# BadgeSMD3.net
KiCad netlist of a schematic drawn in EAGLE
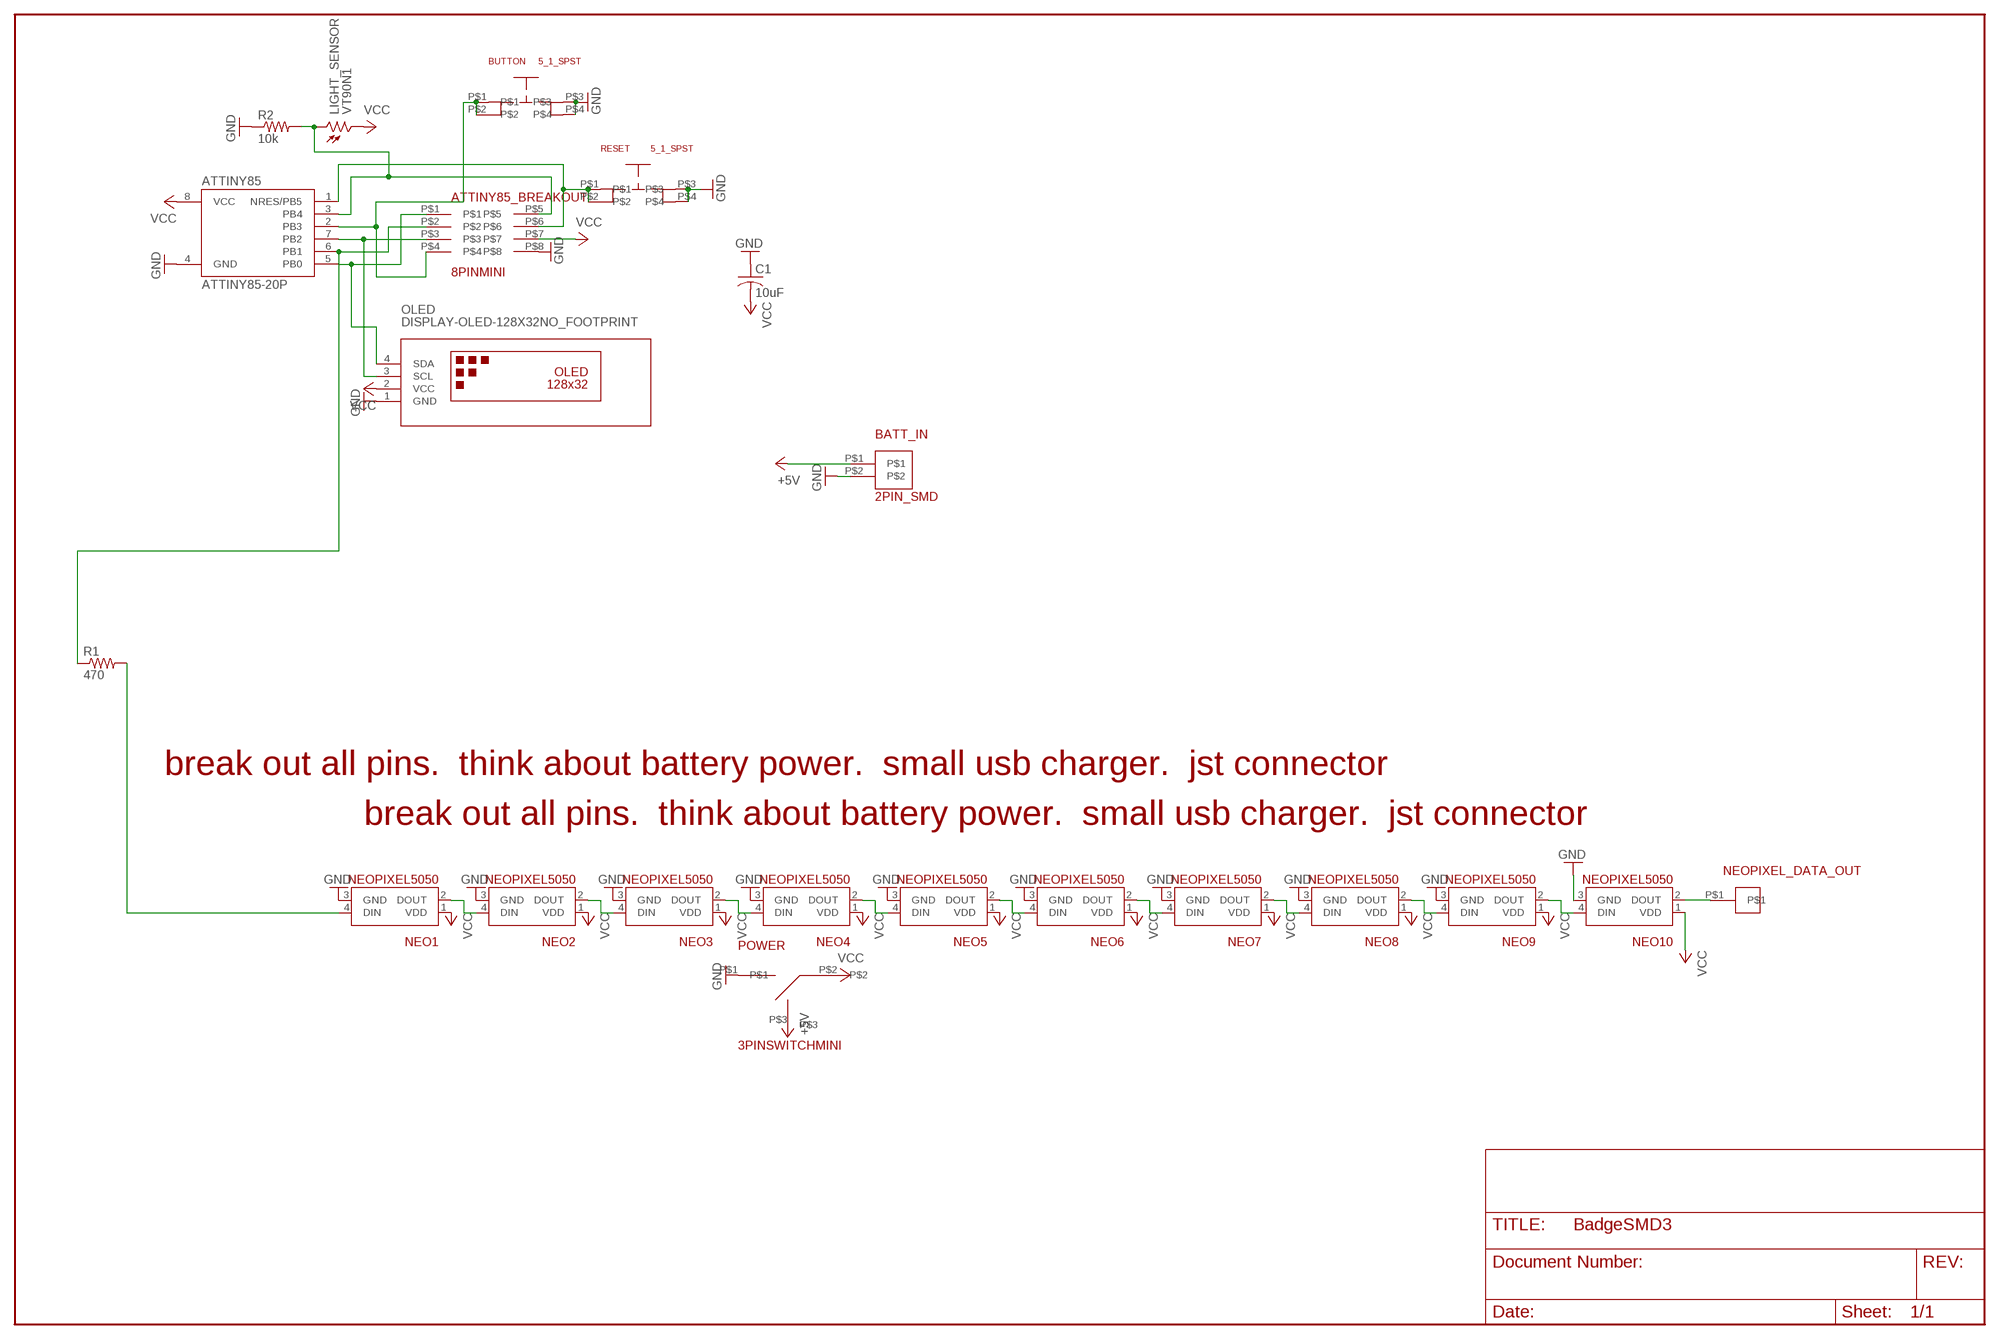
[diagram p0: schematic, sheet 1]

(export (version "E")
  (design (tool "Eeschema 10.0.6"))
  (components
    (comp (ref "ATTINY85")
      (value "ATTINY85-20P")
      (footprint "eagle-import:PDIP08_300MIL")
      (libsource (lib "eagle-import") (part "ATTINY85P-20"))
    )
    (comp (ref "ATTINY85_BREAKOUT")
      (value "8PINMINI")
      (footprint "eagle-import:8PINMINI")
      (libsource (lib "eagle-import") (part "8PINMINI"))
    )
    (comp (ref "BATT_IN")
      (value "2PIN_SMD")
      (footprint "eagle-import:2PIN_SMD")
      (libsource (lib "eagle-import") (part "2PIN_SMD"))
    )
    (comp (ref "BUTTON")
      (value "5_1_SPST")
      (footprint "eagle-import:5_1_SPST")
      (libsource (lib "eagle-import") (part "5_1_SPST"))
    )
    (comp (ref "C1")
      (value "10uF")
      (footprint "eagle-import:C0805")
      (libsource (lib "eagle-import") (part "C-USC0805"))
    )
    (comp (ref "LIGHT_SENSOR")
      (value "VT90N1")
      (footprint "eagle-import:VT900")
      (libsource (lib "eagle-import") (part "VT90N1"))
    )
    (comp (ref "NEO1")
      (value "NEOPIXEL5050")
      (footprint "eagle-import:NEOPIXEL5050")
      (libsource (lib "eagle-import") (part "NEOPIXEL5050"))
    )
    (comp (ref "NEO2")
      (value "NEOPIXEL5050")
      (footprint "eagle-import:NEOPIXEL5050")
      (libsource (lib "eagle-import") (part "NEOPIXEL5050"))
    )
    (comp (ref "NEO3")
      (value "NEOPIXEL5050")
      (footprint "eagle-import:NEOPIXEL5050")
      (libsource (lib "eagle-import") (part "NEOPIXEL5050"))
    )
    (comp (ref "NEO4")
      (value "NEOPIXEL5050")
      (footprint "eagle-import:NEOPIXEL5050")
      (libsource (lib "eagle-import") (part "NEOPIXEL5050"))
    )
    (comp (ref "NEO5")
      (value "NEOPIXEL5050")
      (footprint "eagle-import:NEOPIXEL5050")
      (libsource (lib "eagle-import") (part "NEOPIXEL5050"))
    )
    (comp (ref "NEO6")
      (value "NEOPIXEL5050")
      (footprint "eagle-import:NEOPIXEL5050")
      (libsource (lib "eagle-import") (part "NEOPIXEL5050"))
    )
    (comp (ref "NEO7")
      (value "NEOPIXEL5050")
      (footprint "eagle-import:NEOPIXEL5050")
      (libsource (lib "eagle-import") (part "NEOPIXEL5050"))
    )
    (comp (ref "NEO8")
      (value "NEOPIXEL5050")
      (footprint "eagle-import:NEOPIXEL5050")
      (libsource (lib "eagle-import") (part "NEOPIXEL5050"))
    )
    (comp (ref "NEO9")
      (value "NEOPIXEL5050")
      (footprint "eagle-import:NEOPIXEL5050")
      (libsource (lib "eagle-import") (part "NEOPIXEL5050"))
    )
    (comp (ref "NEO10")
      (value "NEOPIXEL5050")
      (footprint "eagle-import:NEOPIXEL5050")
      (libsource (lib "eagle-import") (part "NEOPIXEL5050"))
    )
    (comp (ref "NEOPIXEL_DATA_OUT")
      (value "1PINMINI")
      (footprint "eagle-import:1PINMINI")
      (libsource (lib "eagle-import") (part "1PINMINI"))
    )
    (comp (ref "OLED")
      (value "DISPLAY-OLED-128X32NO_FOOTPRINT")
      (footprint "eagle-import:DISPLAY-OLED-128X32_NO_FOOTPRINT")
      (libsource (lib "eagle-import") (part "DISPLAY-OLED-128X32NO_FOOTPRINT"))
    )
    (comp (ref "POWER")
      (value "3PINSWITCHMINI")
      (footprint "eagle-import:3PINMINI")
      (libsource (lib "eagle-import") (part "3PINSWITCHMINI"))
    )
    (comp (ref "R1")
      (value "470")
      (footprint "eagle-import:M0805")
      (libsource (lib "eagle-import") (part "R-US_M0805"))
    )
    (comp (ref "R2")
      (value "10k")
      (footprint "eagle-import:M0805")
      (libsource (lib "eagle-import") (part "R-US_M0805"))
    )
    (comp (ref "RESET")
      (value "5_1_SPST")
      (footprint "eagle-import:5_1_SPST")
      (libsource (lib "eagle-import") (part "5_1_SPST"))
    )
  )
  (nets
    (net (code "1") (name "+5V") (class "Default")
      (node (ref "BATT_IN") (pin "P$1") (pinfunction "P$1_P$1") (pintype "bidirectional"))
      (node (ref "POWER") (pin "P$3") (pinfunction "P$3_P$3") (pintype "bidirectional"))
    )
    (net (code "2") (name "GND") (class "Default")
      (node (ref "ATTINY85") (pin "4") (pinfunction "GND_4") (pintype "power_in"))
      (node (ref "ATTINY85_BREAKOUT") (pin "P$8") (pinfunction "P$8_P$8") (pintype "bidirectional"))
      (node (ref "BATT_IN") (pin "P$2") (pinfunction "P$2_P$2") (pintype "bidirectional"))
      (node (ref "BUTTON") (pin "P$3") (pinfunction "P$3_P$3") (pintype "bidirectional"))
      (node (ref "BUTTON") (pin "P$4") (pinfunction "P$4_P$4") (pintype "bidirectional"))
      (node (ref "C1") (pin "1") (pinfunction "1_1") (pintype "passive"))
      (node (ref "NEO1") (pin "3") (pinfunction "GND_3") (pintype "bidirectional"))
      (node (ref "NEO10") (pin "3") (pinfunction "GND_3") (pintype "bidirectional"))
      (node (ref "NEO2") (pin "3") (pinfunction "GND_3") (pintype "bidirectional"))
      (node (ref "NEO3") (pin "3") (pinfunction "GND_3") (pintype "bidirectional"))
      (node (ref "NEO4") (pin "3") (pinfunction "GND_3") (pintype "bidirectional"))
      (node (ref "NEO5") (pin "3") (pinfunction "GND_3") (pintype "bidirectional"))
      (node (ref "NEO6") (pin "3") (pinfunction "GND_3") (pintype "bidirectional"))
      (node (ref "NEO7") (pin "3") (pinfunction "GND_3") (pintype "bidirectional"))
      (node (ref "NEO8") (pin "3") (pinfunction "GND_3") (pintype "bidirectional"))
      (node (ref "NEO9") (pin "3") (pinfunction "GND_3") (pintype "bidirectional"))
      (node (ref "OLED") (pin "1") (pinfunction "GND_1") (pintype "power_in"))
      (node (ref "POWER") (pin "P$1") (pinfunction "P$1_P$1") (pintype "bidirectional"))
      (node (ref "R2") (pin "1") (pinfunction "1_1") (pintype "passive"))
      (node (ref "RESET") (pin "P$3") (pinfunction "P$3_P$3") (pintype "bidirectional"))
      (node (ref "RESET") (pin "P$4") (pinfunction "P$4_P$4") (pintype "bidirectional"))
    )
    (net (code "3") (name "Net-(ATTINY85-NRES{slash}PB5)") (class "Default")
      (node (ref "ATTINY85") (pin "1") (pinfunction "NRES/PB5_1") (pintype "bidirectional"))
      (node (ref "ATTINY85_BREAKOUT") (pin "P$6") (pinfunction "P$6_P$6") (pintype "bidirectional"))
      (node (ref "RESET") (pin "P$1") (pinfunction "P$1_P$1") (pintype "bidirectional"))
      (node (ref "RESET") (pin "P$2") (pinfunction "P$2_P$2") (pintype "bidirectional"))
    )
    (net (code "4") (name "Net-(ATTINY85-PB0)") (class "Default")
      (node (ref "ATTINY85") (pin "5") (pinfunction "PB0_5") (pintype "bidirectional"))
      (node (ref "ATTINY85_BREAKOUT") (pin "P$1") (pinfunction "P$1_P$1") (pintype "bidirectional"))
      (node (ref "OLED") (pin "4") (pinfunction "SDA_4") (pintype "bidirectional"))
    )
    (net (code "5") (name "Net-(ATTINY85-PB1)") (class "Default")
      (node (ref "ATTINY85") (pin "6") (pinfunction "PB1_6") (pintype "bidirectional"))
      (node (ref "ATTINY85_BREAKOUT") (pin "P$2") (pinfunction "P$2_P$2") (pintype "bidirectional"))
      (node (ref "R1") (pin "1") (pinfunction "1_1") (pintype "passive"))
    )
    (net (code "6") (name "Net-(ATTINY85-PB2)") (class "Default")
      (node (ref "ATTINY85") (pin "7") (pinfunction "PB2_7") (pintype "bidirectional"))
      (node (ref "ATTINY85_BREAKOUT") (pin "P$3") (pinfunction "P$3_P$3") (pintype "bidirectional"))
      (node (ref "OLED") (pin "3") (pinfunction "SCL_3") (pintype "bidirectional"))
    )
    (net (code "7") (name "Net-(ATTINY85-PB3)") (class "Default")
      (node (ref "ATTINY85") (pin "2") (pinfunction "PB3_2") (pintype "bidirectional"))
      (node (ref "ATTINY85_BREAKOUT") (pin "P$4") (pinfunction "P$4_P$4") (pintype "bidirectional"))
      (node (ref "BUTTON") (pin "P$1") (pinfunction "P$1_P$1") (pintype "bidirectional"))
      (node (ref "BUTTON") (pin "P$2") (pinfunction "P$2_P$2") (pintype "bidirectional"))
    )
    (net (code "8") (name "Net-(ATTINY85-PB4)") (class "Default")
      (node (ref "ATTINY85") (pin "3") (pinfunction "PB4_3") (pintype "bidirectional"))
      (node (ref "ATTINY85_BREAKOUT") (pin "P$5") (pinfunction "P$5_P$5") (pintype "bidirectional"))
      (node (ref "LIGHT_SENSOR") (pin "1") (pinfunction "1_1") (pintype "passive"))
      (node (ref "R2") (pin "2") (pinfunction "2_2") (pintype "passive"))
    )
    (net (code "9") (name "Net-(NEO1-DIN)") (class "Default")
      (node (ref "NEO1") (pin "4") (pinfunction "DIN_4") (pintype "bidirectional"))
      (node (ref "R1") (pin "2") (pinfunction "2_2") (pintype "passive"))
    )
    (net (code "10") (name "Net-(NEO1-DOUT)") (class "Default")
      (node (ref "NEO1") (pin "2") (pinfunction "DOUT_2") (pintype "bidirectional"))
      (node (ref "NEO2") (pin "4") (pinfunction "DIN_4") (pintype "bidirectional"))
    )
    (net (code "11") (name "Net-(NEO2-DOUT)") (class "Default")
      (node (ref "NEO2") (pin "2") (pinfunction "DOUT_2") (pintype "bidirectional"))
      (node (ref "NEO3") (pin "4") (pinfunction "DIN_4") (pintype "bidirectional"))
    )
    (net (code "12") (name "Net-(NEO3-DOUT)") (class "Default")
      (node (ref "NEO3") (pin "2") (pinfunction "DOUT_2") (pintype "bidirectional"))
      (node (ref "NEO4") (pin "4") (pinfunction "DIN_4") (pintype "bidirectional"))
    )
    (net (code "13") (name "Net-(NEO4-DOUT)") (class "Default")
      (node (ref "NEO4") (pin "2") (pinfunction "DOUT_2") (pintype "bidirectional"))
      (node (ref "NEO5") (pin "4") (pinfunction "DIN_4") (pintype "bidirectional"))
    )
    (net (code "14") (name "Net-(NEO5-DOUT)") (class "Default")
      (node (ref "NEO5") (pin "2") (pinfunction "DOUT_2") (pintype "bidirectional"))
      (node (ref "NEO6") (pin "4") (pinfunction "DIN_4") (pintype "bidirectional"))
    )
    (net (code "15") (name "Net-(NEO6-DOUT)") (class "Default")
      (node (ref "NEO6") (pin "2") (pinfunction "DOUT_2") (pintype "bidirectional"))
      (node (ref "NEO7") (pin "4") (pinfunction "DIN_4") (pintype "bidirectional"))
    )
    (net (code "16") (name "Net-(NEO7-DOUT)") (class "Default")
      (node (ref "NEO7") (pin "2") (pinfunction "DOUT_2") (pintype "bidirectional"))
      (node (ref "NEO8") (pin "4") (pinfunction "DIN_4") (pintype "bidirectional"))
    )
    (net (code "17") (name "Net-(NEO8-DOUT)") (class "Default")
      (node (ref "NEO8") (pin "2") (pinfunction "DOUT_2") (pintype "bidirectional"))
      (node (ref "NEO9") (pin "4") (pinfunction "DIN_4") (pintype "bidirectional"))
    )
    (net (code "18") (name "Net-(NEO10-DIN)") (class "Default")
      (node (ref "NEO10") (pin "4") (pinfunction "DIN_4") (pintype "bidirectional"))
      (node (ref "NEO9") (pin "2") (pinfunction "DOUT_2") (pintype "bidirectional"))
    )
    (net (code "19") (name "Net-(NEO10-DOUT)") (class "Default")
      (node (ref "NEO10") (pin "2") (pinfunction "DOUT_2") (pintype "bidirectional"))
      (node (ref "NEOPIXEL_DATA_OUT") (pin "P$1") (pinfunction "P$1_P$1") (pintype "bidirectional"))
    )
    (net (code "20") (name "VCC") (class "Default")
      (node (ref "ATTINY85") (pin "8") (pinfunction "VCC_8") (pintype "power_in"))
      (node (ref "ATTINY85_BREAKOUT") (pin "P$7") (pinfunction "P$7_P$7") (pintype "bidirectional"))
      (node (ref "C1") (pin "2") (pinfunction "2_2") (pintype "passive"))
      (node (ref "LIGHT_SENSOR") (pin "2") (pinfunction "2_2") (pintype "passive"))
      (node (ref "NEO1") (pin "1") (pinfunction "VDD_1") (pintype "bidirectional"))
      (node (ref "NEO10") (pin "1") (pinfunction "VDD_1") (pintype "bidirectional"))
      (node (ref "NEO2") (pin "1") (pinfunction "VDD_1") (pintype "bidirectional"))
      (node (ref "NEO3") (pin "1") (pinfunction "VDD_1") (pintype "bidirectional"))
      (node (ref "NEO4") (pin "1") (pinfunction "VDD_1") (pintype "bidirectional"))
      (node (ref "NEO5") (pin "1") (pinfunction "VDD_1") (pintype "bidirectional"))
      (node (ref "NEO6") (pin "1") (pinfunction "VDD_1") (pintype "bidirectional"))
      (node (ref "NEO7") (pin "1") (pinfunction "VDD_1") (pintype "bidirectional"))
      (node (ref "NEO8") (pin "1") (pinfunction "VDD_1") (pintype "bidirectional"))
      (node (ref "NEO9") (pin "1") (pinfunction "VDD_1") (pintype "bidirectional"))
      (node (ref "OLED") (pin "2") (pinfunction "VCC_2") (pintype "power_in"))
      (node (ref "POWER") (pin "P$2") (pinfunction "P$2_P$2") (pintype "bidirectional"))
    )
  )
)
